# Power_Supply.net
KiCad netlist of a schematic drawn in Altium Designer
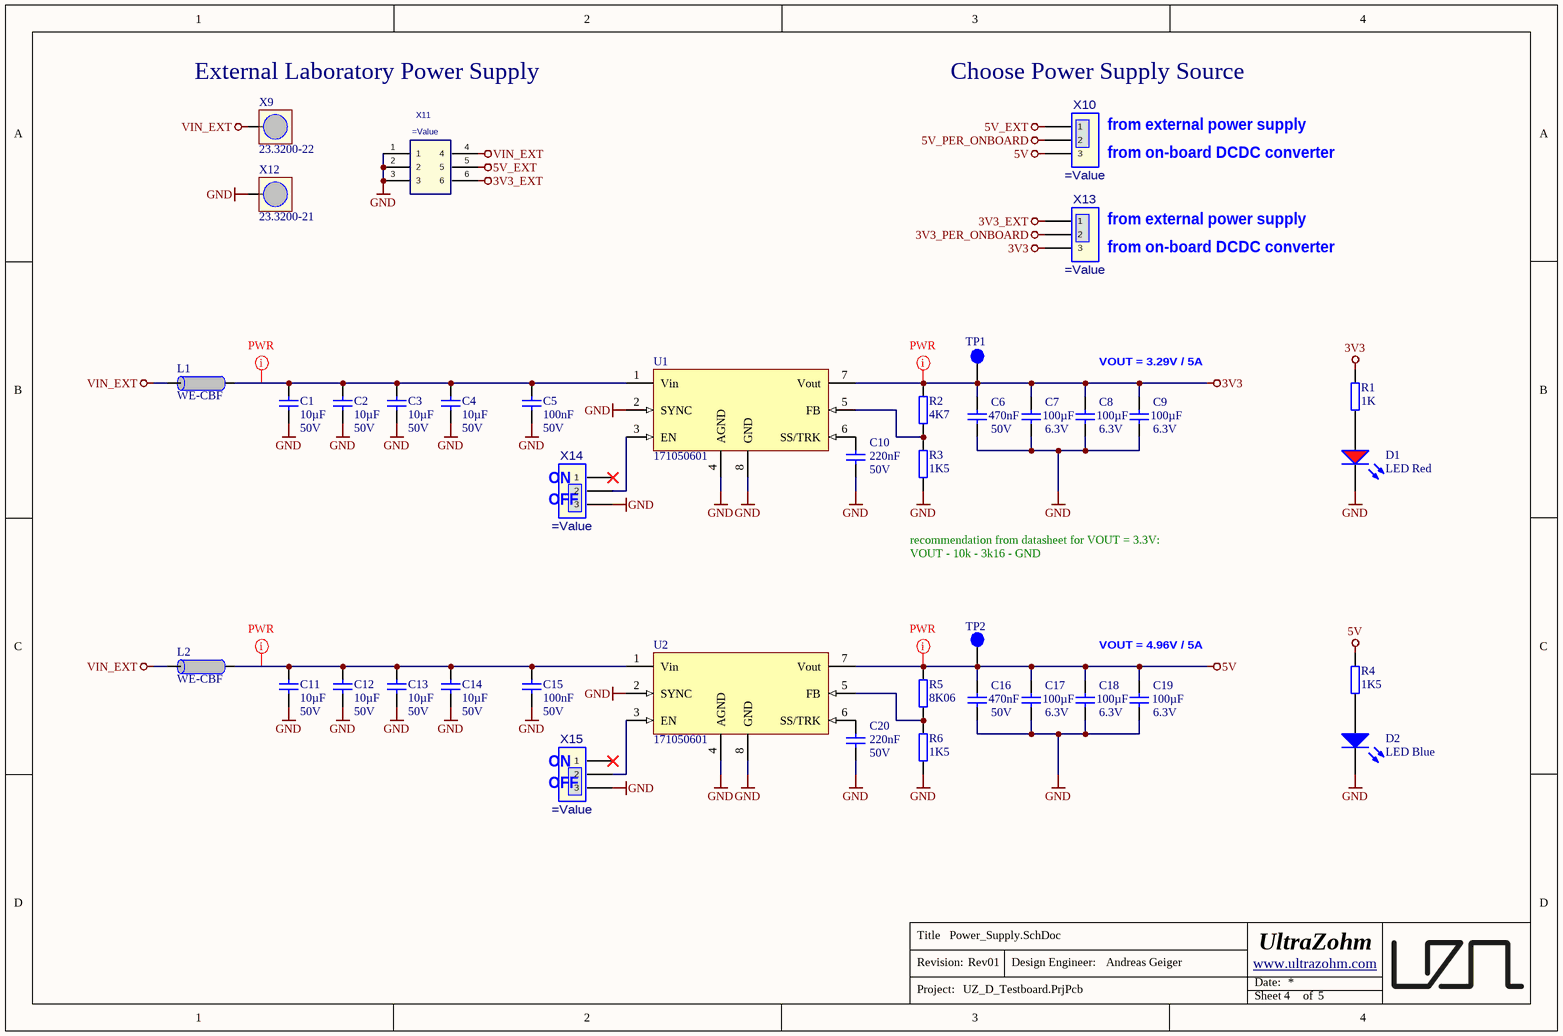
[diagram p0: Power_Supply.SchDoc]

(export (version "E")
  (design (tool "Eeschema 10.0.6"))
  (components
    (comp (ref "C1")
      (value "10µF")
      (footprint "CAPC3216X180N_V")
      (description "KON 10µF 50V X5R 10%  SMD BF 3216 (1206)")
      (fields (field (name "VOLTAGE") "50V") (field (name "TOLERANCE") "10%"))
      (libsource (lib "TE") (part "CAP-NP"))
    )
    (comp (ref "C2")
      (value "10µF")
      (footprint "CAPC3216X180N_V")
      (description "KON 10µF 50V X5R 10%  SMD BF 3216 (1206)")
      (fields (field (name "VOLTAGE") "50V") (field (name "TOLERANCE") "10%"))
      (libsource (lib "TE") (part "CAP-NP"))
    )
    (comp (ref "C3")
      (value "10µF")
      (footprint "CAPC3216X180N_V")
      (description "KON 10µF 50V X5R 10%  SMD BF 3216 (1206)")
      (fields (field (name "VOLTAGE") "50V") (field (name "TOLERANCE") "10%"))
      (libsource (lib "TE") (part "CAP-NP"))
    )
    (comp (ref "C4")
      (value "10µF")
      (footprint "CAPC3216X180N_V")
      (description "KON 10µF 50V X5R 10%  SMD BF 3216 (1206)")
      (fields (field (name "VOLTAGE") "50V") (field (name "TOLERANCE") "10%"))
      (libsource (lib "TE") (part "CAP-NP"))
    )
    (comp (ref "C5")
      (value "100nF")
      (footprint "CAPC1608X90N_V")
      (description "KON 100nF 50V X7R ±10% SMD BF 1608 (0603)")
      (fields (field (name "TOLERANCE") "±10%") (field (name "VOLTAGE") "50V"))
      (libsource (lib "TE") (part "CAP-NP"))
    )
    (comp (ref "C6")
      (value "470nF")
      (footprint "CAPC1608X90N_V")
      (description "KON 470nF 50V X7R SMD  BF 1608 (0603)")
      (fields (field (name "VOLTAGE") "50V"))
      (libsource (lib "TE") (part "CAP-NP"))
    )
    (comp (ref "C7")
      (value "100µF")
      (footprint "CAPC3216X180N_V")
      (description "KON 100µF 6,3V X5R 20% SMD BF 3216 (1206)")
      (fields (field (name "VOLTAGE") "6.3V") (field (name "TOLERANCE") "20%"))
      (libsource (lib "TE") (part "CAP-NP"))
    )
    (comp (ref "C8")
      (value "100µF")
      (footprint "CAPC3216X180N_V")
      (description "KON 100µF 6,3V X5R 20% SMD BF 3216 (1206)")
      (fields (field (name "VOLTAGE") "6.3V") (field (name "TOLERANCE") "20%"))
      (libsource (lib "TE") (part "CAP-NP"))
    )
    (comp (ref "C9")
      (value "100µF")
      (footprint "CAPC3216X180N_V")
      (description "KON 100µF 6,3V X5R 20% SMD BF 3216 (1206)")
      (fields (field (name "VOLTAGE") "6.3V") (field (name "TOLERANCE") "20%"))
      (libsource (lib "TE") (part "CAP-NP"))
    )
    (comp (ref "C10")
      (value "220nF")
      (footprint "CAPC1608X90N_V")
      (description "KON 220nF 50V X7R ±10% SMD BF 1608 (0603)")
      (fields (field (name "TOLERANCE") "±10%") (field (name "VOLTAGE") "50V"))
      (libsource (lib "TE") (part "CAP-NP"))
    )
    (comp (ref "C11")
      (value "10µF")
      (footprint "CAPC3216X180N_V")
      (description "KON 10µF 50V X5R 10%  SMD BF 3216 (1206)")
      (fields (field (name "VOLTAGE") "50V") (field (name "TOLERANCE") "10%"))
      (libsource (lib "TE") (part "CAP-NP"))
    )
    (comp (ref "C12")
      (value "10µF")
      (footprint "CAPC3216X180N_V")
      (description "KON 10µF 50V X5R 10%  SMD BF 3216 (1206)")
      (fields (field (name "VOLTAGE") "50V") (field (name "TOLERANCE") "10%"))
      (libsource (lib "TE") (part "CAP-NP"))
    )
    (comp (ref "C13")
      (value "10µF")
      (footprint "CAPC3216X180N_V")
      (description "KON 10µF 50V X5R 10%  SMD BF 3216 (1206)")
      (fields (field (name "VOLTAGE") "50V") (field (name "TOLERANCE") "10%"))
      (libsource (lib "TE") (part "CAP-NP"))
    )
    (comp (ref "C14")
      (value "10µF")
      (footprint "CAPC3216X180N_V")
      (description "KON 10µF 50V X5R 10%  SMD BF 3216 (1206)")
      (fields (field (name "VOLTAGE") "50V") (field (name "TOLERANCE") "10%"))
      (libsource (lib "TE") (part "CAP-NP"))
    )
    (comp (ref "C15")
      (value "100nF")
      (footprint "CAPC1608X90N_V")
      (description "KON 100nF 50V X7R ±10% SMD BF 1608 (0603)")
      (fields (field (name "TOLERANCE") "±10%") (field (name "VOLTAGE") "50V"))
      (libsource (lib "TE") (part "CAP-NP"))
    )
    (comp (ref "C16")
      (value "470nF")
      (footprint "CAPC1608X90N_V")
      (description "KON 470nF 50V X7R SMD  BF 1608 (0603)")
      (fields (field (name "VOLTAGE") "50V"))
      (libsource (lib "TE") (part "CAP-NP"))
    )
    (comp (ref "C17")
      (value "100µF")
      (footprint "CAPC3216X180N_V")
      (description "KON 100µF 6,3V X5R 20% SMD BF 3216 (1206)")
      (fields (field (name "VOLTAGE") "6.3V") (field (name "TOLERANCE") "20%"))
      (libsource (lib "TE") (part "CAP-NP"))
    )
    (comp (ref "C18")
      (value "100µF")
      (footprint "CAPC3216X180N_V")
      (description "KON 100µF 6,3V X5R 20% SMD BF 3216 (1206)")
      (fields (field (name "VOLTAGE") "6.3V") (field (name "TOLERANCE") "20%"))
      (libsource (lib "TE") (part "CAP-NP"))
    )
    (comp (ref "C19")
      (value "100µF")
      (footprint "CAPC3216X180N_V")
      (description "KON 100µF 6,3V X5R 20% SMD BF 3216 (1206)")
      (fields (field (name "VOLTAGE") "6.3V") (field (name "TOLERANCE") "20%"))
      (libsource (lib "TE") (part "CAP-NP"))
    )
    (comp (ref "C20")
      (value "220nF")
      (footprint "CAPC1608X90N_V")
      (description "KON 220nF 50V X7R ±10% SMD BF 1608 (0603)")
      (fields (field (name "TOLERANCE") "±10%") (field (name "VOLTAGE") "50V"))
      (libsource (lib "TE") (part "CAP-NP"))
    )
    (comp (ref "D1")
      (value "LED Red")
      (footprint "WL-SMCW_0603")
      (description "LED RED 520~625NM 90~100MCD@20MA TOP VIEW 0603 ROHS")
      (fields
        (field (name "MANUFACTURER PART NUMBER") "KT-0603R")
        (field (name "MANUFACTURER") "Hubei KENTO Elec")
        (field (name "CREATED FROM") "T. Wendt")
      )
      (libsource (lib "user") (part "LED_Red"))
    )
    (comp (ref "D2")
      (value "LED Blue")
      (footprint "WL-SMCW_0603")
      (description "LED BLUE 465~475NM 11.5~28.5MCD@5MA TOP VIEW 0603 ROHS")
      (fields
        (field (name "MANUFACTURER PART NUMBER") "19-217/BHC-ZL1M2RY/3T")
        (field (name "MANUFACTURER") "Everlight Elec")
        (field (name "CREATED FROM") "T. Wendt")
      )
      (libsource (lib "user") (part "LED_Blue"))
    )
    (comp (ref "L1")
      (value "WE-CBF")
      (footprint "INDC2012X92N_V")
      (description "Ferritdurchführung SMD 0805")
      (fields (field (name "VOLTAGE") "2000mA"))
      (libsource (lib "TE") (part "Ferritperle"))
    )
    (comp (ref "L2")
      (value "WE-CBF")
      (footprint "INDC2012X92N_V")
      (description "Ferritdurchführung SMD 0805")
      (fields (field (name "VOLTAGE") "2000mA"))
      (libsource (lib "TE") (part "Ferritperle"))
    )
    (comp (ref "R1")
      (value "1K")
      (footprint "RESC1608X55N_V")
      (description "WID SMD 1K 1% 0,1W")
      (fields (field (name "TOLERANCE") "1%"))
      (libsource (lib "TE") (part "RES"))
    )
    (comp (ref "R2")
      (value "4K7")
      (footprint "RESC1608X55N_V")
      (description "WID SMD 4K7 1% 0,1W BF 1608 (0603)")
      (fields (field (name "TOLERANCE") "1%"))
      (libsource (lib "TE") (part "RES"))
    )
    (comp (ref "R3")
      (value "1K5")
      (footprint "RESC1608X55N_V")
      (description "WID SMD 1K5 1% 0,1W")
      (fields (field (name "TOLERANCE") "1%"))
      (libsource (lib "TE") (part "RES"))
    )
    (comp (ref "R4")
      (value "1K5")
      (footprint "RESC1608X55N_V")
      (description "WID SMD 1K5 1% 0,1W")
      (fields (field (name "TOLERANCE") "1%"))
      (libsource (lib "TE") (part "RES"))
    )
    (comp (ref "R5")
      (value "8K06")
      (footprint "RESC1608X55N_V")
      (description "WID SMD 8K06 1% 0,1W BF 1608 (0603)")
      (fields (field (name "TOLERANCE") "1%"))
      (libsource (lib "TE") (part "RES"))
    )
    (comp (ref "R6")
      (value "1K5")
      (footprint "RESC1608X55N_V")
      (description "WID SMD 1K5 1% 0,1W")
      (fields (field (name "TOLERANCE") "1%"))
      (libsource (lib "TE") (part "RES"))
    )
    (comp (ref "TP1") (value "Testpoint 1mm") (footprint "TP_1mm") (libsource (lib "TE") (part "TP")))
    (comp (ref "TP2") (value "Testpoint 1mm") (footprint "TP_1mm") (libsource (lib "TE") (part "TP")))
    (comp (ref "U1")
      (value "171050601")
      (footprint "7TO-PMOD")
      (fields (field (name "VOLTAGE") "Adj."))
      (libsource (lib "TE") (part "WE-DCDC-171050601"))
    )
    (comp (ref "U2")
      (value "171050601")
      (footprint "7TO-PMOD")
      (fields (field (name "VOLTAGE") "Adj."))
      (libsource (lib "TE") (part "WE-DCDC-171050601"))
    )
    (comp (ref "X9")
      (value "23.3200-22")
      (footprint "Bannanenbuchse Rot Stäubli 23.3200-22")
      (description "MULTI-CONTACT   23.3200-22   BANANA SOCKET, 24A, 4MM, THT, R/A, RED")
      (fields (field (name "MANUFACTURER") "Stäubli"))
      (libsource (lib "UZ_D_Testboard") (part "Banannenstecker-Buchse Stäubli Rot"))
    )
    (comp (ref "X10")
      (value "~")
      (footprint "TSW-103-XX-XXX-S")
      (description ".025[0.64] SQ. POST TERMINAL STRIP ASSEMBLY.")
      (fields
        (field (name "MANUFACTURER") "SAMTEC")
        (field (name "MPN") "TSW-103-07-F-S")
        (field (name "CREATED") "2020_11_26_AGeiger")
      )
      (libsource (lib "UZ_D_Testboard") (part "TSW-103-XX-XXX-S"))
    )
    (comp (ref "X11")
      (value "~")
      (footprint "IPL1-103-01-L-D-RA-K")
      (description "2.54mm Double Row Terminal Assembly")
      (fields (field (name "MF") "SAMTEC") (field (name "CREATED") "2018_05_02_AGeiger"))
      (libsource (lib "UZ_D_Testboard") (part "IPL1-103-XX-X-D-X"))
    )
    (comp (ref "X12")
      (value "23.3200-21")
      (footprint "Bannanenbuchse Schwarz Stäubli 23.3200-21")
      (description "MULTI-CONTACT   23.3200-21   BANANA SOCKET, 24A, 4MM, THT, R/A, Black")
      (fields (field (name "MANUFACTURER") "Stäubli"))
      (libsource (lib "UZ_D_Testboard") (part "Banannenstecker-Buchse Stäubli Schwarz"))
    )
    (comp (ref "X13")
      (value "~")
      (footprint "TSW-103-XX-XXX-S")
      (description ".025[0.64] SQ. POST TERMINAL STRIP ASSEMBLY.")
      (fields
        (field (name "MANUFACTURER") "SAMTEC")
        (field (name "MPN") "TSW-103-07-F-S")
        (field (name "CREATED") "2020_11_26_AGeiger")
      )
      (libsource (lib "UZ_D_Testboard") (part "TSW-103-XX-XXX-S"))
    )
    (comp (ref "X14")
      (value "~")
      (footprint "TSW-103-XX-XXX-S")
      (description ".025[0.64] SQ. POST TERMINAL STRIP ASSEMBLY.")
      (fields
        (field (name "MANUFACTURER") "SAMTEC")
        (field (name "MPN") "TSW-103-07-F-S")
        (field (name "CREATED") "2020_11_26_AGeiger")
      )
      (libsource (lib "") (part "TSW-103-XX-XXX-S_1"))
    )
    (comp (ref "X15")
      (value "~")
      (footprint "TSW-103-XX-XXX-S")
      (description ".025[0.64] SQ. POST TERMINAL STRIP ASSEMBLY.")
      (fields
        (field (name "MANUFACTURER") "SAMTEC")
        (field (name "MPN") "TSW-103-07-F-S")
        (field (name "CREATED") "2020_11_26_AGeiger")
      )
      (libsource (lib "") (part "TSW-103-XX-XXX-S_1"))
    )
  )
  (nets
    (net (code "1") (name "3V3") (class "Default")
      (node (ref "C6") (pin "1") (pinfunction "1_1") (pintype "passive"))
      (node (ref "C7") (pin "1") (pinfunction "1_1") (pintype "passive"))
      (node (ref "C8") (pin "1") (pinfunction "1_1") (pintype "passive"))
      (node (ref "C9") (pin "1") (pinfunction "1_1") (pintype "passive"))
      (node (ref "R1") (pin "2") (pinfunction "2_2") (pintype "passive"))
      (node (ref "R2") (pin "2") (pinfunction "2_2") (pintype "passive"))
      (node (ref "TP1") (pin "1") (pintype "passive"))
      (node (ref "U1") (pin "7") (pinfunction "Vout_7") (pintype "power_in"))
      (node (ref "X13") (pin "3") (pinfunction "3_3") (pintype "passive"))
    )
    (net (code "2") (name "3V3_EXT") (class "Default")
      (node (ref "X11") (pin "6") (pinfunction "6_6") (pintype "passive"))
      (node (ref "X13") (pin "1") (pinfunction "1_1") (pintype "passive"))
    )
    (net (code "3") (name "3V3_PER_ONBOARD") (class "Default")
      (node (ref "X13") (pin "2") (pinfunction "2_2") (pintype "passive"))
    )
    (net (code "4") (name "5V") (class "Default")
      (node (ref "C16") (pin "1") (pinfunction "1_1") (pintype "passive"))
      (node (ref "C17") (pin "1") (pinfunction "1_1") (pintype "passive"))
      (node (ref "C18") (pin "1") (pinfunction "1_1") (pintype "passive"))
      (node (ref "C19") (pin "1") (pinfunction "1_1") (pintype "passive"))
      (node (ref "R4") (pin "2") (pinfunction "2_2") (pintype "passive"))
      (node (ref "R5") (pin "2") (pinfunction "2_2") (pintype "passive"))
      (node (ref "TP2") (pin "1") (pintype "passive"))
      (node (ref "U2") (pin "7") (pinfunction "Vout_7") (pintype "power_in"))
      (node (ref "X10") (pin "3") (pinfunction "3_3") (pintype "passive"))
    )
    (net (code "5") (name "5V_EXT") (class "Default")
      (node (ref "X10") (pin "1") (pinfunction "1_1") (pintype "passive"))
      (node (ref "X11") (pin "5") (pinfunction "5_5") (pintype "passive"))
    )
    (net (code "6") (name "5V_PER_ONBOARD") (class "Default")
      (node (ref "X10") (pin "2") (pinfunction "2_2") (pintype "passive"))
    )
    (net (code "7") (name "GND") (class "Default")
      (node (ref "C1") (pin "2") (pinfunction "2_2") (pintype "passive"))
      (node (ref "C10") (pin "2") (pinfunction "2_2") (pintype "passive"))
      (node (ref "C11") (pin "2") (pinfunction "2_2") (pintype "passive"))
      (node (ref "C12") (pin "2") (pinfunction "2_2") (pintype "passive"))
      (node (ref "C13") (pin "2") (pinfunction "2_2") (pintype "passive"))
      (node (ref "C14") (pin "2") (pinfunction "2_2") (pintype "passive"))
      (node (ref "C15") (pin "1") (pinfunction "1_1") (pintype "passive"))
      (node (ref "C16") (pin "2") (pinfunction "2_2") (pintype "passive"))
      (node (ref "C17") (pin "2") (pinfunction "2_2") (pintype "passive"))
      (node (ref "C18") (pin "2") (pinfunction "2_2") (pintype "passive"))
      (node (ref "C19") (pin "2") (pinfunction "2_2") (pintype "passive"))
      (node (ref "C2") (pin "2") (pinfunction "2_2") (pintype "passive"))
      (node (ref "C20") (pin "2") (pinfunction "2_2") (pintype "passive"))
      (node (ref "C3") (pin "2") (pinfunction "2_2") (pintype "passive"))
      (node (ref "C4") (pin "2") (pinfunction "2_2") (pintype "passive"))
      (node (ref "C5") (pin "1") (pinfunction "1_1") (pintype "passive"))
      (node (ref "C6") (pin "2") (pinfunction "2_2") (pintype "passive"))
      (node (ref "C7") (pin "2") (pinfunction "2_2") (pintype "passive"))
      (node (ref "C8") (pin "2") (pinfunction "2_2") (pintype "passive"))
      (node (ref "C9") (pin "2") (pinfunction "2_2") (pintype "passive"))
      (node (ref "D1") (pin "1") (pinfunction "K_1") (pintype "passive"))
      (node (ref "D2") (pin "1") (pinfunction "K_1") (pintype "passive"))
      (node (ref "R3") (pin "1") (pinfunction "1_1") (pintype "passive"))
      (node (ref "R6") (pin "2") (pinfunction "2_2") (pintype "passive"))
      (node (ref "U1") (pin "2") (pinfunction "SYNC_2") (pintype "input"))
      (node (ref "U1") (pin "4") (pinfunction "AGND_4") (pintype "power_in"))
      (node (ref "U1") (pin "8") (pinfunction "GND_8") (pintype "power_in"))
      (node (ref "U2") (pin "2") (pinfunction "SYNC_2") (pintype "input"))
      (node (ref "U2") (pin "4") (pinfunction "AGND_4") (pintype "power_in"))
      (node (ref "U2") (pin "8") (pinfunction "GND_8") (pintype "power_in"))
      (node (ref "X11") (pin "1") (pinfunction "1_1") (pintype "passive"))
      (node (ref "X11") (pin "2") (pinfunction "2_2") (pintype "passive"))
      (node (ref "X11") (pin "3") (pinfunction "3_3") (pintype "passive"))
      (node (ref "X12") (pin "1") (pinfunction "1_1") (pintype "passive"))
      (node (ref "X14") (pin "3") (pinfunction "3_3") (pintype "passive"))
      (node (ref "X15") (pin "3") (pinfunction "3_3") (pintype "passive"))
    )
    (net (code "8") (name "Net-(D1-A)") (class "Default")
      (node (ref "D1") (pin "2") (pinfunction "A_2") (pintype "passive"))
      (node (ref "R1") (pin "1") (pinfunction "1_1") (pintype "passive"))
    )
    (net (code "9") (name "Net-(D2-A)") (class "Default")
      (node (ref "D2") (pin "2") (pinfunction "A_2") (pintype "passive"))
      (node (ref "R4") (pin "1") (pinfunction "1_1") (pintype "passive"))
    )
    (net (code "10") (name "Net-(U1-EN)") (class "Default")
      (node (ref "U1") (pin "3") (pinfunction "EN_3") (pintype "input"))
      (node (ref "X14") (pin "2") (pinfunction "2_2") (pintype "passive"))
    )
    (net (code "11") (name "Net-(U1-FB)") (class "Default")
      (node (ref "R2") (pin "1") (pinfunction "1_1") (pintype "passive"))
      (node (ref "R3") (pin "2") (pinfunction "2_2") (pintype "passive"))
      (node (ref "U1") (pin "5") (pinfunction "FB_5") (pintype "input"))
    )
    (net (code "12") (name "Net-(U1-SS{slash}TRK)") (class "Default")
      (node (ref "C10") (pin "1") (pinfunction "1_1") (pintype "passive"))
      (node (ref "U1") (pin "6") (pinfunction "SS/TRK_6") (pintype "input"))
    )
    (net (code "13") (name "Net-(U1-Vin)") (class "Default")
      (node (ref "C1") (pin "1") (pinfunction "1_1") (pintype "passive"))
      (node (ref "C2") (pin "1") (pinfunction "1_1") (pintype "passive"))
      (node (ref "C3") (pin "1") (pinfunction "1_1") (pintype "passive"))
      (node (ref "C4") (pin "1") (pinfunction "1_1") (pintype "passive"))
      (node (ref "C5") (pin "2") (pinfunction "2_2") (pintype "passive"))
      (node (ref "L1") (pin "1") (pinfunction "1_1") (pintype "passive"))
      (node (ref "U1") (pin "1") (pinfunction "Vin_1") (pintype "power_in"))
    )
    (net (code "14") (name "Net-(U2-EN)") (class "Default")
      (node (ref "U2") (pin "3") (pinfunction "EN_3") (pintype "input"))
      (node (ref "X15") (pin "2") (pinfunction "2_2") (pintype "passive"))
    )
    (net (code "15") (name "Net-(U2-FB)") (class "Default")
      (node (ref "R5") (pin "1") (pinfunction "1_1") (pintype "passive"))
      (node (ref "R6") (pin "1") (pinfunction "1_1") (pintype "passive"))
      (node (ref "U2") (pin "5") (pinfunction "FB_5") (pintype "input"))
    )
    (net (code "16") (name "Net-(U2-SS{slash}TRK)") (class "Default")
      (node (ref "C20") (pin "1") (pinfunction "1_1") (pintype "passive"))
      (node (ref "U2") (pin "6") (pinfunction "SS/TRK_6") (pintype "input"))
    )
    (net (code "17") (name "Net-(U2-Vin)") (class "Default")
      (node (ref "C11") (pin "1") (pinfunction "1_1") (pintype "passive"))
      (node (ref "C12") (pin "1") (pinfunction "1_1") (pintype "passive"))
      (node (ref "C13") (pin "1") (pinfunction "1_1") (pintype "passive"))
      (node (ref "C14") (pin "1") (pinfunction "1_1") (pintype "passive"))
      (node (ref "C15") (pin "2") (pinfunction "2_2") (pintype "passive"))
      (node (ref "L2") (pin "1") (pinfunction "1_1") (pintype "passive"))
      (node (ref "U2") (pin "1") (pinfunction "Vin_1") (pintype "power_in"))
    )
    (net (code "18") (name "VIN_EXT") (class "Default")
      (node (ref "L1") (pin "2") (pinfunction "2_2") (pintype "passive"))
      (node (ref "L2") (pin "2") (pinfunction "2_2") (pintype "passive"))
      (node (ref "X11") (pin "4") (pinfunction "4_4") (pintype "passive"))
      (node (ref "X9") (pin "1") (pinfunction "1_1") (pintype "passive"))
    )
    (net (code "19") (name "unconnected-(X14-Pad1)") (class "Default")
      (node (ref "X14") (pin "1") (pinfunction "1_1") (pintype "passive+no_connect"))
    )
    (net (code "20") (name "unconnected-(X15-Pad1)") (class "Default")
      (node (ref "X15") (pin "1") (pinfunction "1_1") (pintype "passive+no_connect"))
    )
  )
)
